# USB_LiPoPower.net
KiCad netlist of a schematic drawn in EAGLE
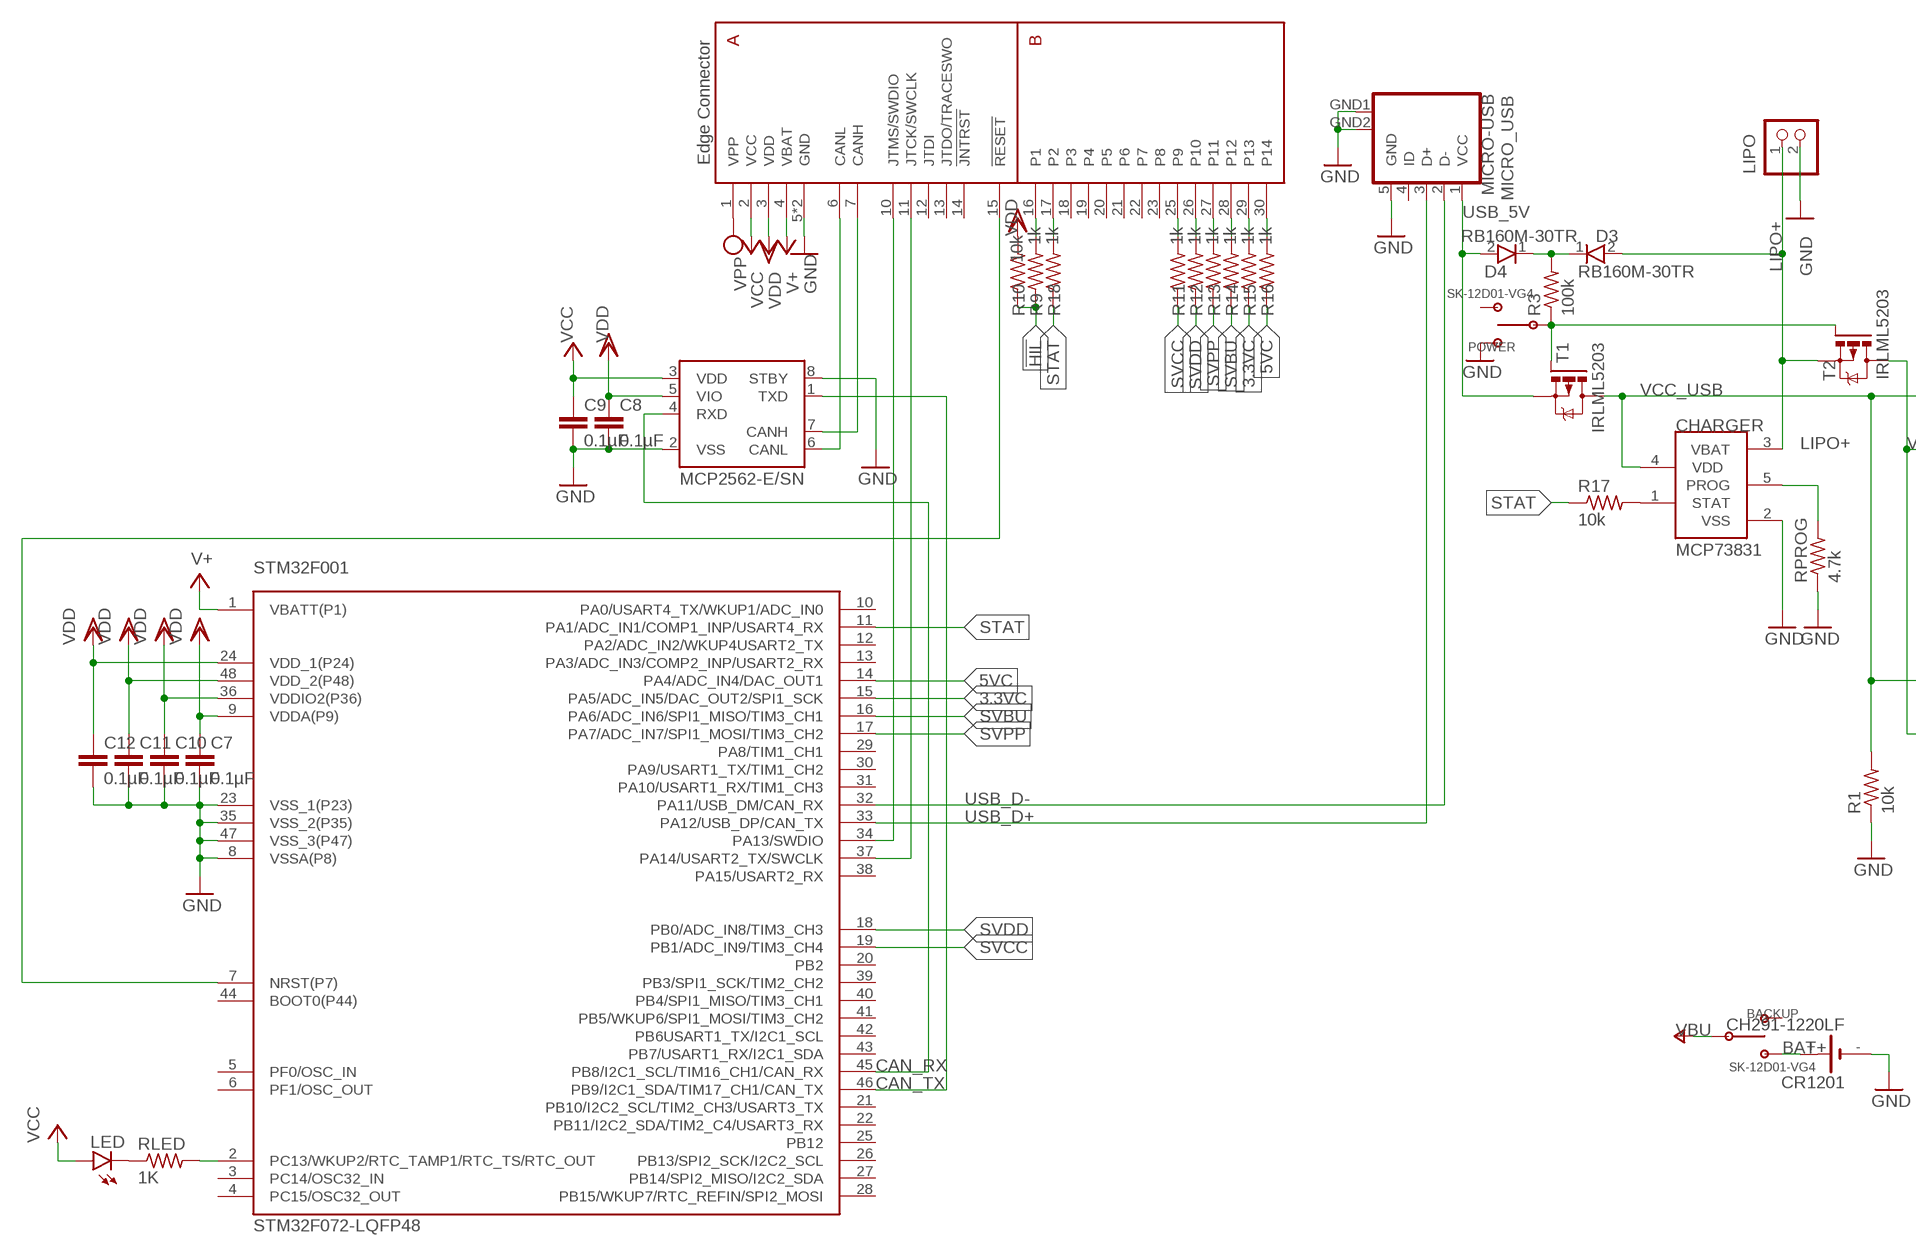
[diagram p0: schematic, sheet 1, part 1 of 2]
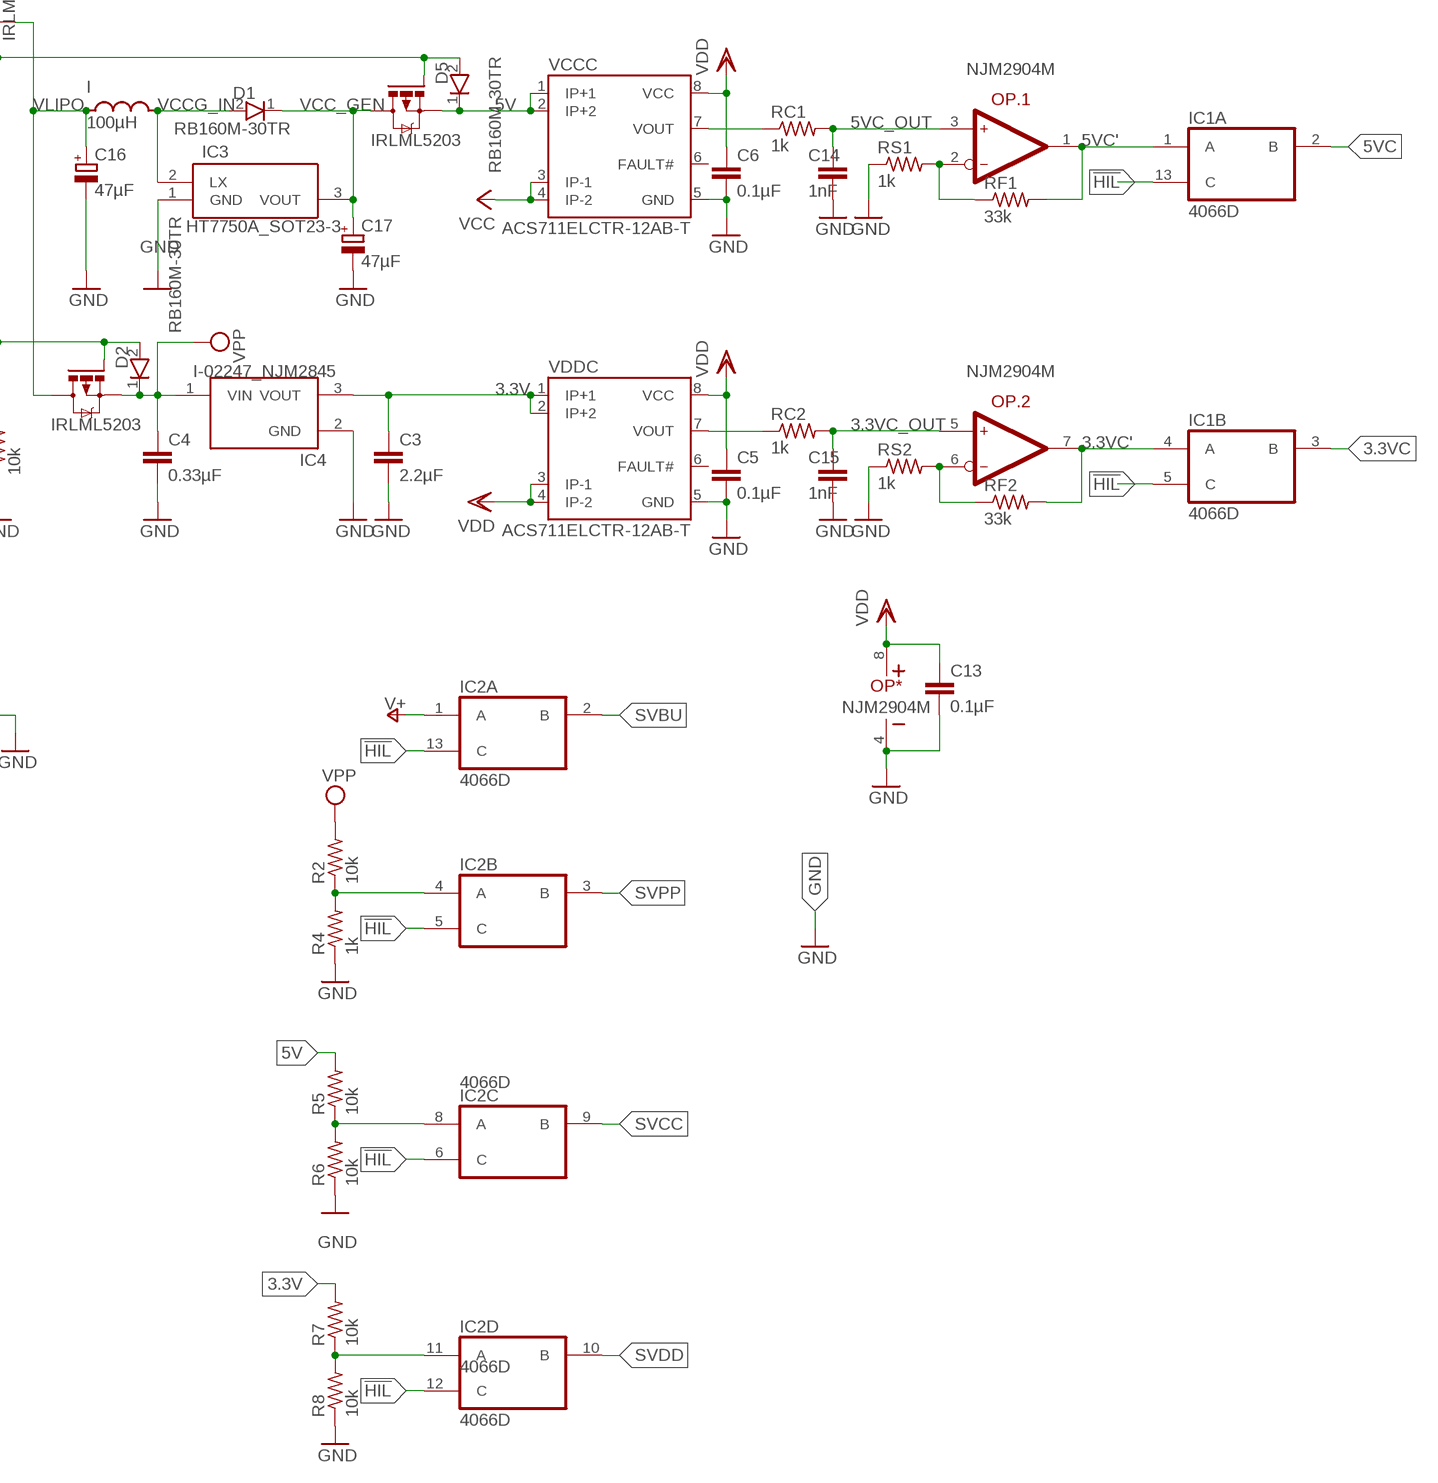
[diagram p1: schematic, sheet 1, part 2 of 2]

(export (version "E")
  (design (tool "Eeschema 10.0.6"))
  (components
    (comp (ref "BACKUP")
      (value "SK-12D01-VG4")
      (footprint "eagle-import:SK-12D01-VG4")
      (libsource (lib "eagle-import") (part "SK-12D01-VG4"))
    )
    (comp (ref "C3")
      (value "2.2µF")
      (footprint "eagle-import:C0603K")
      (libsource (lib "eagle-import") (part "C-EUC0603K"))
    )
    (comp (ref "C4")
      (value "0.33µF")
      (footprint "eagle-import:C0603K")
      (libsource (lib "eagle-import") (part "C-EUC0603K"))
    )
    (comp (ref "C5")
      (value "0.1µF")
      (footprint "eagle-import:C0603K")
      (libsource (lib "eagle-import") (part "C-EUC0603K"))
    )
    (comp (ref "C6")
      (value "0.1µF")
      (footprint "eagle-import:C0603K")
      (libsource (lib "eagle-import") (part "C-EUC0603K"))
    )
    (comp (ref "C7")
      (value "0.1µF")
      (footprint "eagle-import:C0603K")
      (libsource (lib "eagle-import") (part "C-EUC0603K"))
    )
    (comp (ref "C8")
      (value "0.1µF")
      (footprint "eagle-import:C0603K")
      (libsource (lib "eagle-import") (part "C-EUC0603K"))
    )
    (comp (ref "C9")
      (value "0.1µF")
      (footprint "eagle-import:C0603K")
      (libsource (lib "eagle-import") (part "C-EUC0603K"))
    )
    (comp (ref "C10")
      (value "0.1µF")
      (footprint "eagle-import:C0603K")
      (libsource (lib "eagle-import") (part "C-EUC0603K"))
    )
    (comp (ref "C11")
      (value "0.1µF")
      (footprint "eagle-import:C0603K")
      (libsource (lib "eagle-import") (part "C-EUC0603K"))
    )
    (comp (ref "C12")
      (value "0.1µF")
      (footprint "eagle-import:C0603K")
      (libsource (lib "eagle-import") (part "C-EUC0603K"))
    )
    (comp (ref "C13")
      (value "0.1µF")
      (footprint "eagle-import:C0603K")
      (libsource (lib "eagle-import") (part "C-EUC0603K"))
    )
    (comp (ref "C14")
      (value "1nF")
      (footprint "eagle-import:C0603K")
      (libsource (lib "eagle-import") (part "C-EUC0603K"))
    )
    (comp (ref "C15")
      (value "1nF")
      (footprint "eagle-import:C0603K")
      (libsource (lib "eagle-import") (part "C-EUC0603K"))
    )
    (comp (ref "C16")
      (value "47µF")
      (footprint "eagle-import:UD-5X5,8_NICHICON")
      (libsource (lib "eagle-import") (part "CPOL-EUUD-5X5,8"))
    )
    (comp (ref "C17")
      (value "47µF")
      (footprint "eagle-import:UD-5X5,8_NICHICON")
      (libsource (lib "eagle-import") (part "CPOL-EUUD-5X5,8"))
    )
    (comp (ref "CHARGER")
      (value "MCP73831")
      (footprint "eagle-import:SOT23-5L")
      (libsource (lib "eagle-import") (part "MCP73831"))
    )
    (comp (ref "CR1201")
      (value "CH291-1220LF")
      (footprint "eagle-import:CH291-1220LF")
      (libsource (lib "eagle-import") (part "CH291-1220LF"))
    )
    (comp (ref "D1")
      (value "RB160M-30TR")
      (footprint "eagle-import:SODFL3516X90N")
      (fields (field (name "MOUSER_PART_NUMBER") "755-RB160M-30TR") (field (name "RS_PART_NUMBER") "7526079"))
      (libsource (lib "eagle-import") (part "RB160M-30TR"))
    )
    (comp (ref "D2")
      (value "RB160M-30TR")
      (footprint "eagle-import:SODFL3516X90N")
      (fields (field (name "MOUSER_PART_NUMBER") "755-RB160M-30TR") (field (name "RS_PART_NUMBER") "7526079"))
      (libsource (lib "eagle-import") (part "RB160M-30TR"))
    )
    (comp (ref "D3")
      (value "RB160M-30TR")
      (footprint "eagle-import:SODFL3516X90N")
      (fields (field (name "MOUSER_PART_NUMBER") "755-RB160M-30TR") (field (name "RS_PART_NUMBER") "7526079"))
      (libsource (lib "eagle-import") (part "RB160M-30TR"))
    )
    (comp (ref "D4")
      (value "RB160M-30TR")
      (footprint "eagle-import:SODFL3516X90N")
      (fields (field (name "MOUSER_PART_NUMBER") "755-RB160M-30TR") (field (name "RS_PART_NUMBER") "7526079"))
      (libsource (lib "eagle-import") (part "RB160M-30TR"))
    )
    (comp (ref "D5")
      (value "RB160M-30TR")
      (footprint "eagle-import:SODFL3516X90N")
      (fields (field (name "MOUSER_PART_NUMBER") "755-RB160M-30TR") (field (name "RS_PART_NUMBER") "7526079"))
      (libsource (lib "eagle-import") (part "RB160M-30TR"))
    )
    (comp (ref "I")
      (value "100µH")
      (footprint "eagle-import:NR10050")
      (libsource (lib "eagle-import") (part "NR10050"))
    )
    (comp (ref "IC1")
      (value "4066D")
      (footprint "eagle-import:SO14")
      (libsource (lib "eagle-import") (part "4066D"))
    )
    (comp (ref "IC2")
      (value "4066D")
      (footprint "eagle-import:SO14")
      (libsource (lib "eagle-import") (part "4066D"))
    )
    (comp (ref "IC3")
      (value "HT7750A_SOT23-3")
      (footprint "eagle-import:SOT95P190X145-3N")
      (fields (field (name "MANUFACTURER_PART_NUMBER") "HT7750A SOT23-3"))
      (libsource (lib "eagle-import") (part "HT7750A_SOT23-3"))
    )
    (comp (ref "IC4")
      (value "I-02247_NJM2845")
      (footprint "eagle-import:TO252")
      (libsource (lib "eagle-import") (part "I-02247_NJM2845"))
    )
    (comp (ref "LED")
      (value "LEDCHIP-LED0603")
      (footprint "eagle-import:CHIP-LED0603")
      (libsource (lib "eagle-import") (part "LEDCHIP-LED0603"))
    )
    (comp (ref "LIPO")
      (value "S2B-PH-K-S")
      (footprint "eagle-import:S2B-PH-K-S")
      (libsource (lib "eagle-import") (part "S2B-PH-K-S"))
    )
    (comp (ref "MCP2562")
      (value "MCP2562-E/SN")
      (footprint "eagle-import:SOIC127P600X175-8N")
      (fields (field (name "MF") "Microchip"))
      (libsource (lib "eagle-import") (part "MCP2562-E/SN"))
    )
    (comp (ref "MICRO_USB")
      (value "MICRO-USB")
      (footprint "eagle-import:MICRO-USB")
      (libsource (lib "eagle-import") (part "MICRO-USB"))
    )
    (comp (ref "OP")
      (value "NJM2904M")
      (footprint "eagle-import:SO-8")
      (libsource (lib "eagle-import") (part "NJM2904M"))
    )
    (comp (ref "POWER")
      (value "SK-12D01-VG4")
      (footprint "eagle-import:SK-12D01-VG4")
      (libsource (lib "eagle-import") (part "SK-12D01-VG4"))
    )
    (comp (ref "R1")
      (value "10k")
      (footprint "eagle-import:R0603")
      (libsource (lib "eagle-import") (part "R-US_R0603"))
    )
    (comp (ref "R2")
      (value "10k")
      (footprint "eagle-import:R0603")
      (libsource (lib "eagle-import") (part "R-US_R0603"))
    )
    (comp (ref "R3")
      (value "100k")
      (footprint "eagle-import:R0603")
      (libsource (lib "eagle-import") (part "R-US_R0603"))
    )
    (comp (ref "R4")
      (value "1k")
      (footprint "eagle-import:R0603")
      (libsource (lib "eagle-import") (part "R-US_R0603"))
    )
    (comp (ref "R5")
      (value "10k")
      (footprint "eagle-import:R0603")
      (libsource (lib "eagle-import") (part "R-US_R0603"))
    )
    (comp (ref "R6")
      (value "10k")
      (footprint "eagle-import:R0603")
      (libsource (lib "eagle-import") (part "R-US_R0603"))
    )
    (comp (ref "R7")
      (value "10k")
      (footprint "eagle-import:R0603")
      (libsource (lib "eagle-import") (part "R-US_R0603"))
    )
    (comp (ref "R8")
      (value "10k")
      (footprint "eagle-import:R0603")
      (libsource (lib "eagle-import") (part "R-US_R0603"))
    )
    (comp (ref "R9")
      (value "1k")
      (footprint "eagle-import:R0603")
      (libsource (lib "eagle-import") (part "resistor_348_R-US_R0603"))
    )
    (comp (ref "R10")
      (value "10k")
      (footprint "eagle-import:R0603")
      (libsource (lib "eagle-import") (part "resistor_348_R-US_R0603"))
    )
    (comp (ref "R11")
      (value "1k")
      (footprint "eagle-import:R0603")
      (libsource (lib "eagle-import") (part "resistor_348_R-US_R0603"))
    )
    (comp (ref "R12")
      (value "1k")
      (footprint "eagle-import:R0603")
      (libsource (lib "eagle-import") (part "resistor_348_R-US_R0603"))
    )
    (comp (ref "R13")
      (value "1k")
      (footprint "eagle-import:R0603")
      (libsource (lib "eagle-import") (part "resistor_348_R-US_R0603"))
    )
    (comp (ref "R14")
      (value "1k")
      (footprint "eagle-import:R0603")
      (libsource (lib "eagle-import") (part "resistor_348_R-US_R0603"))
    )
    (comp (ref "R15")
      (value "1k")
      (footprint "eagle-import:R0603")
      (libsource (lib "eagle-import") (part "resistor_348_R-US_R0603"))
    )
    (comp (ref "R16")
      (value "1k")
      (footprint "eagle-import:R0603")
      (libsource (lib "eagle-import") (part "resistor_348_R-US_R0603"))
    )
    (comp (ref "R17")
      (value "10k")
      (footprint "eagle-import:R0603")
      (libsource (lib "eagle-import") (part "resistor_348_R-US_R0603"))
    )
    (comp (ref "R18")
      (value "1k")
      (footprint "eagle-import:R0603")
      (libsource (lib "eagle-import") (part "resistor_348_R-US_R0603"))
    )
    (comp (ref "RC1")
      (value "1k")
      (footprint "eagle-import:R0603")
      (libsource (lib "eagle-import") (part "R-US_R0603"))
    )
    (comp (ref "RC2")
      (value "1k")
      (footprint "eagle-import:R0603")
      (libsource (lib "eagle-import") (part "R-US_R0603"))
    )
    (comp (ref "RF1")
      (value "33k")
      (footprint "eagle-import:R0603")
      (libsource (lib "eagle-import") (part "R-US_R0603"))
    )
    (comp (ref "RF2")
      (value "33k")
      (footprint "eagle-import:R0603")
      (libsource (lib "eagle-import") (part "R-US_R0603"))
    )
    (comp (ref "RLED")
      (value "1K")
      (footprint "eagle-import:R0603")
      (libsource (lib "eagle-import") (part "R-US_R0603"))
    )
    (comp (ref "RPROG")
      (value "4.7k")
      (footprint "eagle-import:R0603")
      (libsource (lib "eagle-import") (part "R-US_R0603"))
    )
    (comp (ref "RS1")
      (value "1k")
      (footprint "eagle-import:R0603")
      (libsource (lib "eagle-import") (part "R-US_R0603"))
    )
    (comp (ref "RS2")
      (value "1k")
      (footprint "eagle-import:R0603")
      (libsource (lib "eagle-import") (part "R-US_R0603"))
    )
    (comp (ref "STM32F001")
      (value "STM32F072-LQFP48")
      (footprint "eagle-import:LQFP48")
      (libsource (lib "eagle-import") (part "STM32F072-LQFP48"))
    )
    (comp (ref "T1")
      (value "IRLML5203")
      (footprint "eagle-import:MICRO3")
      (libsource (lib "eagle-import") (part "IRLML5203"))
    )
    (comp (ref "T2")
      (value "IRLML5203")
      (footprint "eagle-import:MICRO3")
      (libsource (lib "eagle-import") (part "IRLML5203"))
    )
    (comp (ref "T3")
      (value "IRLML5203")
      (footprint "eagle-import:MICRO3")
      (libsource (lib "eagle-import") (part "IRLML5203"))
    )
    (comp (ref "T4")
      (value "IRLML5203")
      (footprint "eagle-import:MICRO3")
      (libsource (lib "eagle-import") (part "IRLML5203"))
    )
    (comp (ref "U$2")
      (value "EDGE30")
      (footprint "eagle-import:EDGE30")
      (libsource (lib "eagle-import") (part "EDGE30"))
    )
    (comp (ref "VCCC")
      (value "ACS711ELCTR-12AB-T")
      (footprint "eagle-import:SOIC8")
      (libsource (lib "eagle-import") (part "ACS711ELC?TR-12AB-T"))
    )
    (comp (ref "VDDC")
      (value "ACS711ELCTR-12AB-T")
      (footprint "eagle-import:SOIC8")
      (libsource (lib "eagle-import") (part "ACS711ELC?TR-12AB-T"))
    )
  )
  (nets
    (net (code "1") (name "/3.3VC'") (class "Default")
      (node (ref "IC1") (pin "4") (pinfunction "A_4") (pintype "tri_state"))
      (node (ref "OP") (pin "7") (pinfunction "OUT_7") (pintype "output"))
      (node (ref "RF2") (pin "2") (pinfunction "2_2") (pintype "passive"))
    )
    (net (code "2") (name "/3.3VC_OUT") (class "Default")
      (node (ref "C15") (pin "1") (pinfunction "1_1") (pintype "passive"))
      (node (ref "OP") (pin "5") (pinfunction "IN+_5") (pintype "input"))
      (node (ref "RC2") (pin "2") (pinfunction "2_2") (pintype "passive"))
    )
    (net (code "3") (name "/5VC'") (class "Default")
      (node (ref "IC1") (pin "1") (pinfunction "A_1") (pintype "tri_state"))
      (node (ref "OP") (pin "1") (pinfunction "OUT_1") (pintype "output"))
      (node (ref "RF1") (pin "2") (pinfunction "2_2") (pintype "passive"))
    )
    (net (code "4") (name "/5VC_OUT") (class "Default")
      (node (ref "C14") (pin "1") (pinfunction "1_1") (pintype "passive"))
      (node (ref "OP") (pin "3") (pinfunction "IN+_3") (pintype "input"))
      (node (ref "RC1") (pin "2") (pinfunction "2_2") (pintype "passive"))
    )
    (net (code "5") (name "/BAT+") (class "Default")
      (node (ref "BACKUP") (pin "B") (pinfunction "B_B") (pintype "bidirectional"))
      (node (ref "CR1201") (pin "+") (pinfunction "+_+") (pintype "passive"))
    )
    (net (code "6") (name "/CAN_RX") (class "Default")
      (node (ref "MCP2562") (pin "4") (pinfunction "RXD_4") (pintype "output"))
      (node (ref "STM32F001") (pin "45") (pinfunction "PB8/I2C1_SCL/TIM16_CH1/CAN_RX_45") (pintype "bidirectional"))
    )
    (net (code "7") (name "/CAN_TX") (class "Default")
      (node (ref "MCP2562") (pin "1") (pinfunction "TXD_1") (pintype "input"))
      (node (ref "STM32F001") (pin "46") (pinfunction "PB9/I2C1_SDA/TIM17_CH1/CAN_TX_46") (pintype "bidirectional"))
    )
    (net (code "8") (name "/LIPO+") (class "Default")
      (node (ref "CHARGER") (pin "3") (pinfunction "VBAT_3") (pintype "bidirectional"))
      (node (ref "D3") (pin "2") (pinfunction "A_2") (pintype "bidirectional"))
      (node (ref "LIPO") (pin "1") (pinfunction "1_1") (pintype "passive"))
      (node (ref "T2") (pin "2") (pinfunction "S_2") (pintype "passive"))
    )
    (net (code "9") (name "/USB_5V") (class "Default")
      (node (ref "D4") (pin "2") (pinfunction "A_2") (pintype "bidirectional"))
      (node (ref "MICRO_USB") (pin "1") (pinfunction "VCC_1") (pintype "power_in"))
      (node (ref "T1") (pin "2") (pinfunction "S_2") (pintype "passive"))
    )
    (net (code "10") (name "/USB_D+") (class "Default")
      (node (ref "MICRO_USB") (pin "3") (pinfunction "D+_3") (pintype "bidirectional"))
      (node (ref "STM32F001") (pin "33") (pinfunction "PA12/USB_DP/CAN_TX_33") (pintype "bidirectional"))
    )
    (net (code "11") (name "/USB_D-") (class "Default")
      (node (ref "MICRO_USB") (pin "2") (pinfunction "D-_2") (pintype "bidirectional"))
      (node (ref "STM32F001") (pin "32") (pinfunction "PA11/USB_DM/CAN_RX_32") (pintype "bidirectional"))
    )
    (net (code "12") (name "/VCCG_IN") (class "Default")
      (node (ref "D1") (pin "2") (pinfunction "A_2") (pintype "bidirectional"))
      (node (ref "I") (pin "2") (pinfunction "2_2") (pintype "bidirectional"))
      (node (ref "IC3") (pin "2") (pinfunction "LX_2") (pintype "bidirectional"))
    )
    (net (code "13") (name "/VCC_GEN") (class "Default")
      (node (ref "C17") (pin "+") (pinfunction "+_+") (pintype "passive"))
      (node (ref "D1") (pin "1") (pinfunction "K_1") (pintype "bidirectional"))
      (node (ref "IC3") (pin "3") (pinfunction "VOUT_3") (pintype "bidirectional"))
      (node (ref "T3") (pin "3") (pinfunction "D_3") (pintype "passive"))
    )
    (net (code "14") (name "/VCC_USB") (class "Default")
      (node (ref "CHARGER") (pin "4") (pinfunction "VDD_4") (pintype "bidirectional"))
      (node (ref "D2") (pin "2") (pinfunction "A_2") (pintype "bidirectional"))
      (node (ref "D5") (pin "2") (pinfunction "A_2") (pintype "bidirectional"))
      (node (ref "R1") (pin "2") (pinfunction "2_2") (pintype "passive"))
      (node (ref "T1") (pin "3") (pinfunction "D_3") (pintype "passive"))
      (node (ref "T3") (pin "1") (pinfunction "G_1") (pintype "passive"))
      (node (ref "T4") (pin "1") (pinfunction "G_1") (pintype "passive"))
    )
    (net (code "15") (name "/VLIPO") (class "Default")
      (node (ref "C16") (pin "+") (pinfunction "+_+") (pintype "passive"))
      (node (ref "I") (pin "1") (pinfunction "1_1") (pintype "bidirectional"))
      (node (ref "T2") (pin "3") (pinfunction "D_3") (pintype "passive"))
      (node (ref "T4") (pin "3") (pinfunction "D_3") (pintype "passive"))
    )
    (net (code "16") (name "/~{HIL}") (class "Default")
      (node (ref "IC1") (pin "13") (pinfunction "C_13") (pintype "input"))
      (node (ref "IC1") (pin "5") (pinfunction "C_5") (pintype "input"))
      (node (ref "IC2") (pin "12") (pinfunction "C_12") (pintype "input"))
      (node (ref "IC2") (pin "13") (pinfunction "C_13") (pintype "input"))
      (node (ref "IC2") (pin "5") (pinfunction "C_5") (pintype "input"))
      (node (ref "IC2") (pin "6") (pinfunction "C_6") (pintype "input"))
      (node (ref "R10") (pin "1") (pinfunction "1_1") (pintype "passive"))
      (node (ref "R9") (pin "1") (pinfunction "1_1") (pintype "passive"))
    )
    (net (code "17") (name "3.3V") (class "Default")
      (node (ref "C3") (pin "1") (pinfunction "1_1") (pintype "passive"))
      (node (ref "IC4") (pin "3") (pinfunction "VOUT_3") (pintype "bidirectional"))
      (node (ref "R7") (pin "2") (pinfunction "2_2") (pintype "passive"))
      (node (ref "VDDC") (pin "1") (pinfunction "IP+1_1") (pintype "bidirectional"))
      (node (ref "VDDC") (pin "2") (pinfunction "IP+2_2") (pintype "bidirectional"))
    )
    (net (code "18") (name "3.3VC") (class "Default")
      (node (ref "IC1") (pin "3") (pinfunction "B_3") (pintype "tri_state"))
      (node (ref "R15") (pin "1") (pinfunction "1_1") (pintype "passive"))
      (node (ref "STM32F001") (pin "15") (pinfunction "PA5/ADC_IN5/DAC_OUT2/SPI1_SCK_15") (pintype "bidirectional"))
    )
    (net (code "19") (name "5V") (class "Default")
      (node (ref "D5") (pin "1") (pinfunction "K_1") (pintype "bidirectional"))
      (node (ref "R5") (pin "2") (pinfunction "2_2") (pintype "passive"))
      (node (ref "T3") (pin "2") (pinfunction "S_2") (pintype "passive"))
      (node (ref "VCCC") (pin "1") (pinfunction "IP+1_1") (pintype "bidirectional"))
      (node (ref "VCCC") (pin "2") (pinfunction "IP+2_2") (pintype "bidirectional"))
    )
    (net (code "20") (name "5VC") (class "Default")
      (node (ref "IC1") (pin "2") (pinfunction "B_2") (pintype "tri_state"))
      (node (ref "R16") (pin "1") (pinfunction "1_1") (pintype "passive"))
      (node (ref "STM32F001") (pin "14") (pinfunction "PA4/ADC_IN4/DAC_OUT1_14") (pintype "bidirectional"))
    )
    (net (code "21") (name "GND") (class "Default")
      (node (ref "C10") (pin "2") (pinfunction "2_2") (pintype "passive"))
      (node (ref "C11") (pin "2") (pinfunction "2_2") (pintype "passive"))
      (node (ref "C12") (pin "2") (pinfunction "2_2") (pintype "passive"))
      (node (ref "C13") (pin "2") (pinfunction "2_2") (pintype "passive"))
      (node (ref "C14") (pin "2") (pinfunction "2_2") (pintype "passive"))
      (node (ref "C15") (pin "2") (pinfunction "2_2") (pintype "passive"))
      (node (ref "C16") (pin "-") (pinfunction "-_-") (pintype "passive"))
      (node (ref "C17") (pin "-") (pinfunction "-_-") (pintype "passive"))
      (node (ref "C3") (pin "2") (pinfunction "2_2") (pintype "passive"))
      (node (ref "C4") (pin "2") (pinfunction "2_2") (pintype "passive"))
      (node (ref "C5") (pin "2") (pinfunction "2_2") (pintype "passive"))
      (node (ref "C6") (pin "2") (pinfunction "2_2") (pintype "passive"))
      (node (ref "C7") (pin "2") (pinfunction "2_2") (pintype "passive"))
      (node (ref "C8") (pin "2") (pinfunction "2_2") (pintype "passive"))
      (node (ref "C9") (pin "2") (pinfunction "2_2") (pintype "passive"))
      (node (ref "CHARGER") (pin "2") (pinfunction "VSS_2") (pintype "bidirectional"))
      (node (ref "CR1201") (pin "-") (pinfunction "-_-") (pintype "passive"))
      (node (ref "IC3") (pin "1") (pinfunction "GND_1") (pintype "bidirectional"))
      (node (ref "IC4") (pin "2") (pinfunction "GND_2") (pintype "bidirectional"))
      (node (ref "LIPO") (pin "2") (pinfunction "2_2") (pintype "passive"))
      (node (ref "MCP2562") (pin "2") (pinfunction "VSS_2") (pintype "power_in"))
      (node (ref "MCP2562") (pin "8") (pinfunction "STBY_8") (pintype "input"))
      (node (ref "MICRO_USB") (pin "5") (pinfunction "GND_5") (pintype "power_in"))
      (node (ref "MICRO_USB") (pin "GND1") (pinfunction "GND_GND1") (pintype "power_in"))
      (node (ref "MICRO_USB") (pin "GND2") (pinfunction "GND_GND2") (pintype "power_in"))
      (node (ref "OP") (pin "4") (pinfunction "V-_4") (pintype "power_in"))
      (node (ref "POWER") (pin "A") (pinfunction "A_A") (pintype "bidirectional"))
      (node (ref "R1") (pin "1") (pinfunction "1_1") (pintype "passive"))
      (node (ref "R4") (pin "1") (pinfunction "1_1") (pintype "passive"))
      (node (ref "R6") (pin "1") (pinfunction "1_1") (pintype "passive"))
      (node (ref "R8") (pin "1") (pinfunction "1_1") (pintype "passive"))
      (node (ref "RPROG") (pin "1") (pinfunction "1_1") (pintype "passive"))
      (node (ref "RS1") (pin "1") (pinfunction "1_1") (pintype "passive"))
      (node (ref "RS2") (pin "1") (pinfunction "1_1") (pintype "passive"))
      (node (ref "STM32F001") (pin "23") (pinfunction "VSS_1(P23)_23") (pintype "bidirectional"))
      (node (ref "STM32F001") (pin "35") (pinfunction "VSS_2(P35)_35") (pintype "bidirectional"))
      (node (ref "STM32F001") (pin "47") (pinfunction "VSS_3(P47)_47") (pintype "bidirectional"))
      (node (ref "STM32F001") (pin "8") (pinfunction "VSSA(P8)_8") (pintype "bidirectional"))
      (node (ref "U$2") (pin "5") (pinfunction "GND_5") (pintype "power_in"))
      (node (ref "U$2") (pin "8") (pinfunction "GND_8") (pintype "power_in"))
      (node (ref "VCCC") (pin "5") (pinfunction "GND_5") (pintype "bidirectional"))
      (node (ref "VDDC") (pin "5") (pinfunction "GND_5") (pintype "bidirectional"))
    )
    (net (code "22") (name "Net-(CHARGER-PROG)") (class "Default")
      (node (ref "CHARGER") (pin "5") (pinfunction "PROG_5") (pintype "bidirectional"))
      (node (ref "RPROG") (pin "2") (pinfunction "2_2") (pintype "passive"))
    )
    (net (code "23") (name "Net-(CHARGER-STAT)") (class "Default")
      (node (ref "CHARGER") (pin "1") (pinfunction "STAT_1") (pintype "bidirectional"))
      (node (ref "R17") (pin "2") (pinfunction "2_2") (pintype "passive"))
    )
    (net (code "24") (name "Net-(D3-K)") (class "Default")
      (node (ref "D3") (pin "1") (pinfunction "K_1") (pintype "bidirectional"))
      (node (ref "D4") (pin "1") (pinfunction "K_1") (pintype "bidirectional"))
      (node (ref "R3") (pin "2") (pinfunction "2_2") (pintype "passive"))
    )
    (net (code "25") (name "Net-(IC2B-A)") (class "Default")
      (node (ref "IC2") (pin "4") (pinfunction "A_4") (pintype "tri_state"))
      (node (ref "R2") (pin "1") (pinfunction "1_1") (pintype "passive"))
      (node (ref "R4") (pin "2") (pinfunction "2_2") (pintype "passive"))
    )
    (net (code "26") (name "Net-(IC2C-A)") (class "Default")
      (node (ref "IC2") (pin "8") (pinfunction "A_8") (pintype "tri_state"))
      (node (ref "R5") (pin "1") (pinfunction "1_1") (pintype "passive"))
      (node (ref "R6") (pin "2") (pinfunction "2_2") (pintype "passive"))
    )
    (net (code "27") (name "Net-(IC2D-A)") (class "Default")
      (node (ref "IC2") (pin "11") (pinfunction "A_11") (pintype "tri_state"))
      (node (ref "R7") (pin "1") (pinfunction "1_1") (pintype "passive"))
      (node (ref "R8") (pin "2") (pinfunction "2_2") (pintype "passive"))
    )
    (net (code "28") (name "Net-(LED-PadC)") (class "Default")
      (node (ref "LED") (pin "C") (pinfunction "C_C") (pintype "passive"))
      (node (ref "RLED") (pin "1") (pinfunction "1_1") (pintype "passive"))
    )
    (net (code "29") (name "Net-(MCP2562-CANH)") (class "Default")
      (node (ref "MCP2562") (pin "7") (pinfunction "CANH_7") (pintype "input"))
      (node (ref "U$2") (pin "7") (pinfunction "CANH_7") (pintype "bidirectional"))
    )
    (net (code "30") (name "Net-(MCP2562-CANL)") (class "Default")
      (node (ref "MCP2562") (pin "6") (pinfunction "CANL_6") (pintype "input"))
      (node (ref "U$2") (pin "6") (pinfunction "CANL_6") (pintype "bidirectional"))
    )
    (net (code "31") (name "Net-(OPB-IN-)") (class "Default")
      (node (ref "OP") (pin "2") (pinfunction "IN-_2") (pintype "input"))
      (node (ref "RF1") (pin "1") (pinfunction "1_1") (pintype "passive"))
      (node (ref "RS1") (pin "2") (pinfunction "2_2") (pintype "passive"))
    )
    (net (code "32") (name "Net-(OPC-IN-)") (class "Default")
      (node (ref "OP") (pin "6") (pinfunction "IN-_6") (pintype "input"))
      (node (ref "RF2") (pin "1") (pinfunction "1_1") (pintype "passive"))
      (node (ref "RS2") (pin "2") (pinfunction "2_2") (pintype "passive"))
    )
    (net (code "33") (name "Net-(STM32F001-NRST(P7))") (class "Default")
      (node (ref "STM32F001") (pin "7") (pinfunction "NRST(P7)_7") (pintype "bidirectional"))
      (node (ref "U$2") (pin "15") (pinfunction "~{RESET}_15") (pintype "bidirectional"))
    )
    (net (code "34") (name "Net-(STM32F001-PA13{slash}SWDIO)") (class "Default")
      (node (ref "STM32F001") (pin "34") (pinfunction "PA13/SWDIO_34") (pintype "bidirectional"))
      (node (ref "U$2") (pin "10") (pinfunction "JTMS/SWDIO_10") (pintype "bidirectional"))
    )
    (net (code "35") (name "Net-(STM32F001-PA14{slash}USART2_TX{slash}SWCLK)") (class "Default")
      (node (ref "STM32F001") (pin "37") (pinfunction "PA14/USART2_TX/SWCLK_37") (pintype "bidirectional"))
      (node (ref "U$2") (pin "11") (pinfunction "JTCK/SWCLK_11") (pintype "bidirectional"))
    )
    (net (code "36") (name "Net-(STM32F001-PC13{slash}WKUP2{slash}RTC_TAMP1{slash}RTC_TS{slash}RTC_OUT)") (class "Default")
      (node (ref "RLED") (pin "2") (pinfunction "2_2") (pintype "passive"))
      (node (ref "STM32F001") (pin "2") (pinfunction "PC13/WKUP2/RTC_TAMP1/RTC_TS/RTC_OUT_2") (pintype "bidirectional"))
    )
    (net (code "37") (name "Net-(T1-G)") (class "Default")
      (node (ref "POWER") (pin "C") (pinfunction "C_C") (pintype "bidirectional"))
      (node (ref "R3") (pin "1") (pinfunction "1_1") (pintype "passive"))
      (node (ref "T1") (pin "1") (pinfunction "G_1") (pintype "passive"))
      (node (ref "T2") (pin "1") (pinfunction "G_1") (pintype "passive"))
    )
    (net (code "38") (name "Net-(U$2-P1)") (class "Default")
      (node (ref "R9") (pin "2") (pinfunction "2_2") (pintype "passive"))
      (node (ref "U$2") (pin "16") (pinfunction "P1_16") (pintype "bidirectional"))
    )
    (net (code "39") (name "Net-(U$2-P2)") (class "Default")
      (node (ref "R18") (pin "2") (pinfunction "2_2") (pintype "passive"))
      (node (ref "U$2") (pin "17") (pinfunction "P2_17") (pintype "bidirectional"))
    )
    (net (code "40") (name "Net-(U$2-P9)") (class "Default")
      (node (ref "R11") (pin "2") (pinfunction "2_2") (pintype "passive"))
      (node (ref "U$2") (pin "25") (pinfunction "P9_25") (pintype "bidirectional"))
    )
    (net (code "41") (name "Net-(U$2-P10)") (class "Default")
      (node (ref "R12") (pin "2") (pinfunction "2_2") (pintype "passive"))
      (node (ref "U$2") (pin "26") (pinfunction "P10_26") (pintype "bidirectional"))
    )
    (net (code "42") (name "Net-(U$2-P11)") (class "Default")
      (node (ref "R13") (pin "2") (pinfunction "2_2") (pintype "passive"))
      (node (ref "U$2") (pin "27") (pinfunction "P11_27") (pintype "bidirectional"))
    )
    (net (code "43") (name "Net-(U$2-P12)") (class "Default")
      (node (ref "R14") (pin "2") (pinfunction "2_2") (pintype "passive"))
      (node (ref "U$2") (pin "28") (pinfunction "P12_28") (pintype "bidirectional"))
    )
    (net (code "44") (name "Net-(U$2-P13)") (class "Default")
      (node (ref "R15") (pin "2") (pinfunction "2_2") (pintype "passive"))
      (node (ref "U$2") (pin "29") (pinfunction "P13_29") (pintype "bidirectional"))
    )
    (net (code "45") (name "Net-(U$2-P14)") (class "Default")
      (node (ref "R16") (pin "2") (pinfunction "2_2") (pintype "passive"))
      (node (ref "U$2") (pin "30") (pinfunction "P14_30") (pintype "bidirectional"))
    )
    (net (code "46") (name "Net-(VCCC-VOUT)") (class "Default")
      (node (ref "RC1") (pin "1") (pinfunction "1_1") (pintype "passive"))
      (node (ref "VCCC") (pin "7") (pinfunction "VOUT_7") (pintype "bidirectional"))
    )
    (net (code "47") (name "Net-(VDDC-VOUT)") (class "Default")
      (node (ref "RC2") (pin "1") (pinfunction "1_1") (pintype "passive"))
      (node (ref "VDDC") (pin "7") (pinfunction "VOUT_7") (pintype "bidirectional"))
    )
    (net (code "48") (name "STAT") (class "Default")
      (node (ref "R17") (pin "1") (pinfunction "1_1") (pintype "passive"))
      (node (ref "R18") (pin "1") (pinfunction "1_1") (pintype "passive"))
      (node (ref "STM32F001") (pin "11") (pinfunction "PA1/ADC_IN1/COMP1_INP/USART4_RX_11") (pintype "bidirectional"))
    )
    (net (code "49") (name "SVBU") (class "Default")
      (node (ref "IC2") (pin "2") (pinfunction "B_2") (pintype "tri_state"))
      (node (ref "R14") (pin "1") (pinfunction "1_1") (pintype "passive"))
      (node (ref "STM32F001") (pin "16") (pinfunction "PA6/ADC_IN6/SPI1_MISO/TIM3_CH1_16") (pintype "bidirectional"))
    )
    (net (code "50") (name "SVCC") (class "Default")
      (node (ref "IC2") (pin "9") (pinfunction "B_9") (pintype "tri_state"))
      (node (ref "R11") (pin "1") (pinfunction "1_1") (pintype "passive"))
      (node (ref "STM32F001") (pin "19") (pinfunction "PB1/ADC_IN9/TIM3_CH4_19") (pintype "bidirectional"))
    )
    (net (code "51") (name "SVDD") (class "Default")
      (node (ref "IC2") (pin "10") (pinfunction "B_10") (pintype "tri_state"))
      (node (ref "R12") (pin "1") (pinfunction "1_1") (pintype "passive"))
      (node (ref "STM32F001") (pin "18") (pinfunction "PB0/ADC_IN8/TIM3_CH3_18") (pintype "bidirectional"))
    )
    (net (code "52") (name "SVPP") (class "Default")
      (node (ref "IC2") (pin "3") (pinfunction "B_3") (pintype "tri_state"))
      (node (ref "R13") (pin "1") (pinfunction "1_1") (pintype "passive"))
      (node (ref "STM32F001") (pin "17") (pinfunction "PA7/ADC_IN7/SPI1_MOSI/TIM3_CH2_17") (pintype "bidirectional"))
    )
    (net (code "53") (name "V+") (class "Default")
      (node (ref "BACKUP") (pin "C") (pinfunction "C_C") (pintype "bidirectional"))
      (node (ref "IC2") (pin "1") (pinfunction "A_1") (pintype "tri_state"))
      (node (ref "STM32F001") (pin "1") (pinfunction "VBATT(P1)_1") (pintype "bidirectional"))
      (node (ref "U$2") (pin "4") (pinfunction "VBAT_4") (pintype "power_in"))
    )
    (net (code "54") (name "VCC") (class "Default")
      (node (ref "C9") (pin "1") (pinfunction "1_1") (pintype "passive"))
      (node (ref "LED") (pin "A") (pinfunction "A_A") (pintype "passive"))
      (node (ref "MCP2562") (pin "3") (pinfunction "VDD_3") (pintype "power_in"))
      (node (ref "U$2") (pin "2") (pinfunction "VCC_2") (pintype "power_in"))
      (node (ref "VCCC") (pin "3") (pinfunction "IP-1_3") (pintype "bidirectional"))
      (node (ref "VCCC") (pin "4") (pinfunction "IP-2_4") (pintype "bidirectional"))
    )
    (net (code "55") (name "VDD") (class "Default")
      (node (ref "C10") (pin "1") (pinfunction "1_1") (pintype "passive"))
      (node (ref "C11") (pin "1") (pinfunction "1_1") (pintype "passive"))
      (node (ref "C12") (pin "1") (pinfunction "1_1") (pintype "passive"))
      (node (ref "C13") (pin "1") (pinfunction "1_1") (pintype "passive"))
      (node (ref "C5") (pin "1") (pinfunction "1_1") (pintype "passive"))
      (node (ref "C6") (pin "1") (pinfunction "1_1") (pintype "passive"))
      (node (ref "C7") (pin "1") (pinfunction "1_1") (pintype "passive"))
      (node (ref "C8") (pin "1") (pinfunction "1_1") (pintype "passive"))
      (node (ref "MCP2562") (pin "5") (pinfunction "VIO_5") (pintype "power_in"))
      (node (ref "OP") (pin "8") (pinfunction "V+_8") (pintype "power_in"))
      (node (ref "R10") (pin "2") (pinfunction "2_2") (pintype "passive"))
      (node (ref "STM32F001") (pin "24") (pinfunction "VDD_1(P24)_24") (pintype "bidirectional"))
      (node (ref "STM32F001") (pin "36") (pinfunction "VDDIO2(P36)_36") (pintype "bidirectional"))
      (node (ref "STM32F001") (pin "48") (pinfunction "VDD_2(P48)_48") (pintype "bidirectional"))
      (node (ref "STM32F001") (pin "9") (pinfunction "VDDA(P9)_9") (pintype "bidirectional"))
      (node (ref "U$2") (pin "3") (pinfunction "VDD_3") (pintype "power_in"))
      (node (ref "VCCC") (pin "8") (pinfunction "VCC_8") (pintype "bidirectional"))
      (node (ref "VDDC") (pin "3") (pinfunction "IP-1_3") (pintype "bidirectional"))
      (node (ref "VDDC") (pin "4") (pinfunction "IP-2_4") (pintype "bidirectional"))
      (node (ref "VDDC") (pin "8") (pinfunction "VCC_8") (pintype "bidirectional"))
    )
    (net (code "56") (name "VPP") (class "Default")
      (node (ref "C4") (pin "1") (pinfunction "1_1") (pintype "passive"))
      (node (ref "D2") (pin "1") (pinfunction "K_1") (pintype "bidirectional"))
      (node (ref "IC4") (pin "1") (pinfunction "VIN_1") (pintype "bidirectional"))
      (node (ref "R2") (pin "2") (pinfunction "2_2") (pintype "passive"))
      (node (ref "T4") (pin "2") (pinfunction "S_2") (pintype "passive"))
      (node (ref "U$2") (pin "1") (pinfunction "VPP_1") (pintype "power_in"))
    )
    (net (code "57") (name "unconnected-(BACKUP-PadA)") (class "Default")
      (node (ref "BACKUP") (pin "A") (pinfunction "A_A") (pintype "bidirectional"))
    )
    (net (code "58") (name "unconnected-(MICRO_USB-ID-Pad4)") (class "Default")
      (node (ref "MICRO_USB") (pin "4") (pinfunction "ID_4") (pintype "bidirectional"))
    )
    (net (code "59") (name "unconnected-(POWER-PadB)") (class "Default")
      (node (ref "POWER") (pin "B") (pinfunction "B_B") (pintype "bidirectional"))
    )
    (net (code "60") (name "unconnected-(STM32F001-BOOT0(P44)-Pad44)") (class "Default")
      (node (ref "STM32F001") (pin "44") (pinfunction "BOOT0(P44)_44") (pintype "bidirectional"))
    )
    (net (code "61") (name "unconnected-(STM32F001-PA0{slash}USART4_TX{slash}WKUP1{slash}ADC_IN0-Pad10)") (class "Default")
      (node (ref "STM32F001") (pin "10") (pinfunction "PA0/USART4_TX/WKUP1/ADC_IN0_10") (pintype "bidirectional"))
    )
    (net (code "62") (name "unconnected-(STM32F001-PA2{slash}ADC_IN2{slash}WKUP4USART2_TX-Pad12)") (class "Default")
      (node (ref "STM32F001") (pin "12") (pinfunction "PA2/ADC_IN2/WKUP4USART2_TX_12") (pintype "bidirectional"))
    )
    (net (code "63") (name "unconnected-(STM32F001-PA3{slash}ADC_IN3{slash}COMP2_INP{slash}USART2_RX-Pad13)") (class "Default")
      (node (ref "STM32F001") (pin "13") (pinfunction "PA3/ADC_IN3/COMP2_INP/USART2_RX_13") (pintype "bidirectional"))
    )
    (net (code "64") (name "unconnected-(STM32F001-PA8{slash}TIM1_CH1-Pad29)") (class "Default")
      (node (ref "STM32F001") (pin "29") (pinfunction "PA8/TIM1_CH1_29") (pintype "bidirectional"))
    )
    (net (code "65") (name "unconnected-(STM32F001-PA9{slash}USART1_TX{slash}TIM1_CH2-Pad30)") (class "Default")
      (node (ref "STM32F001") (pin "30") (pinfunction "PA9/USART1_TX/TIM1_CH2_30") (pintype "bidirectional"))
    )
    (net (code "66") (name "unconnected-(STM32F001-PA10{slash}USART1_RX{slash}TIM1_CH3-Pad31)") (class "Default")
      (node (ref "STM32F001") (pin "31") (pinfunction "PA10/USART1_RX/TIM1_CH3_31") (pintype "bidirectional"))
    )
    (net (code "67") (name "unconnected-(STM32F001-PA15{slash}USART2_RX-Pad38)") (class "Default")
      (node (ref "STM32F001") (pin "38") (pinfunction "PA15/USART2_RX_38") (pintype "bidirectional"))
    )
    (net (code "68") (name "unconnected-(STM32F001-PB2-Pad20)") (class "Default")
      (node (ref "STM32F001") (pin "20") (pinfunction "PB2_20") (pintype "bidirectional"))
    )
    (net (code "69") (name "unconnected-(STM32F001-PB3{slash}SPI1_SCK{slash}TIM2_CH2-Pad39)") (class "Default")
      (node (ref "STM32F001") (pin "39") (pinfunction "PB3/SPI1_SCK/TIM2_CH2_39") (pintype "bidirectional"))
    )
    (net (code "70") (name "unconnected-(STM32F001-PB4{slash}SPI1_MISO{slash}TIM3_CH1-Pad40)") (class "Default")
      (node (ref "STM32F001") (pin "40") (pinfunction "PB4/SPI1_MISO/TIM3_CH1_40") (pintype "bidirectional"))
    )
    (net (code "71") (name "unconnected-(STM32F001-PB5{slash}WKUP6{slash}SPI1_MOSI{slash}TIM3_CH2-Pad41)") (class "Default")
      (node (ref "STM32F001") (pin "41") (pinfunction "PB5/WKUP6/SPI1_MOSI/TIM3_CH2_41") (pintype "bidirectional"))
    )
    (net (code "72") (name "unconnected-(STM32F001-PB6USART1_TX{slash}I2C1_SCL-Pad42)") (class "Default")
      (node (ref "STM32F001") (pin "42") (pinfunction "PB6USART1_TX/I2C1_SCL_42") (pintype "bidirectional"))
    )
    (net (code "73") (name "unconnected-(STM32F001-PB7{slash}USART1_RX{slash}I2C1_SDA-Pad43)") (class "Default")
      (node (ref "STM32F001") (pin "43") (pinfunction "PB7/USART1_RX/I2C1_SDA_43") (pintype "bidirectional"))
    )
    (net (code "74") (name "unconnected-(STM32F001-PB10{slash}I2C2_SCL{slash}TIM2_CH3{slash}USART3_TX-Pad21)") (class "Default")
      (node (ref "STM32F001") (pin "21") (pinfunction "PB10/I2C2_SCL/TIM2_CH3/USART3_TX_21") (pintype "bidirectional"))
    )
    (net (code "75") (name "unconnected-(STM32F001-PB11{slash}I2C2_SDA{slash}TIM2_C4{slash}USART3_RX-Pad22)") (class "Default")
      (node (ref "STM32F001") (pin "22") (pinfunction "PB11/I2C2_SDA/TIM2_C4/USART3_RX_22") (pintype "bidirectional"))
    )
    (net (code "76") (name "unconnected-(STM32F001-PB12-Pad25)") (class "Default")
      (node (ref "STM32F001") (pin "25") (pinfunction "PB12_25") (pintype "bidirectional"))
    )
    (net (code "77") (name "unconnected-(STM32F001-PB13{slash}SPI2_SCK{slash}I2C2_SCL-Pad26)") (class "Default")
      (node (ref "STM32F001") (pin "26") (pinfunction "PB13/SPI2_SCK/I2C2_SCL_26") (pintype "bidirectional"))
    )
    (net (code "78") (name "unconnected-(STM32F001-PB14{slash}SPI2_MISO{slash}I2C2_SDA-Pad27)") (class "Default")
      (node (ref "STM32F001") (pin "27") (pinfunction "PB14/SPI2_MISO/I2C2_SDA_27") (pintype "bidirectional"))
    )
    (net (code "79") (name "unconnected-(STM32F001-PB15{slash}WKUP7{slash}RTC_REFIN{slash}SPI2_MOSI-Pad28)") (class "Default")
      (node (ref "STM32F001") (pin "28") (pinfunction "PB15/WKUP7/RTC_REFIN/SPI2_MOSI_28") (pintype "bidirectional"))
    )
    (net (code "80") (name "unconnected-(STM32F001-PC14{slash}OSC32_IN-Pad3)") (class "Default")
      (node (ref "STM32F001") (pin "3") (pinfunction "PC14/OSC32_IN_3") (pintype "bidirectional"))
    )
    (net (code "81") (name "unconnected-(STM32F001-PC15{slash}OSC32_OUT-Pad4)") (class "Default")
      (node (ref "STM32F001") (pin "4") (pinfunction "PC15/OSC32_OUT_4") (pintype "bidirectional"))
    )
    (net (code "82") (name "unconnected-(STM32F001-PF0{slash}OSC_IN-Pad5)") (class "Default")
      (node (ref "STM32F001") (pin "5") (pinfunction "PF0/OSC_IN_5") (pintype "bidirectional"))
    )
    (net (code "83") (name "unconnected-(STM32F001-PF1{slash}OSC_OUT-Pad6)") (class "Default")
      (node (ref "STM32F001") (pin "6") (pinfunction "PF1/OSC_OUT_6") (pintype "bidirectional"))
    )
    (net (code "84") (name "unconnected-(U$2-JTDI-Pad12)") (class "Default")
      (node (ref "U$2") (pin "12") (pinfunction "JTDI_12") (pintype "bidirectional"))
    )
    (net (code "85") (name "unconnected-(U$2-JTDO{slash}TRACESWO-Pad13)") (class "Default")
      (node (ref "U$2") (pin "13") (pinfunction "JTDO/TRACESWO_13") (pintype "bidirectional"))
    )
    (net (code "86") (name "unconnected-(U$2-P3-Pad18)") (class "Default")
      (node (ref "U$2") (pin "18") (pinfunction "P3_18") (pintype "bidirectional"))
    )
    (net (code "87") (name "unconnected-(U$2-P4-Pad19)") (class "Default")
      (node (ref "U$2") (pin "19") (pinfunction "P4_19") (pintype "bidirectional"))
    )
    (net (code "88") (name "unconnected-(U$2-P5-Pad20)") (class "Default")
      (node (ref "U$2") (pin "20") (pinfunction "P5_20") (pintype "bidirectional"))
    )
    (net (code "89") (name "unconnected-(U$2-P6-Pad21)") (class "Default")
      (node (ref "U$2") (pin "21") (pinfunction "P6_21") (pintype "bidirectional"))
    )
    (net (code "90") (name "unconnected-(U$2-P7-Pad22)") (class "Default")
      (node (ref "U$2") (pin "22") (pinfunction "P7_22") (pintype "bidirectional"))
    )
    (net (code "91") (name "unconnected-(U$2-P8-Pad23)") (class "Default")
      (node (ref "U$2") (pin "23") (pinfunction "P8_23") (pintype "bidirectional"))
    )
    (net (code "92") (name "unconnected-(U$2-~{JNTRST}-Pad14)") (class "Default")
      (node (ref "U$2") (pin "14") (pinfunction "~{JNTRST}_14") (pintype "bidirectional"))
    )
    (net (code "93") (name "unconnected-(VCCC-FAULT#-Pad6)") (class "Default")
      (node (ref "VCCC") (pin "6") (pinfunction "FAULT#_6") (pintype "bidirectional"))
    )
    (net (code "94") (name "unconnected-(VDDC-FAULT#-Pad6)") (class "Default")
      (node (ref "VDDC") (pin "6") (pinfunction "FAULT#_6") (pintype "bidirectional"))
    )
  )
)
